# Bluetooth.net
KiCad netlist of a schematic drawn in EAGLE
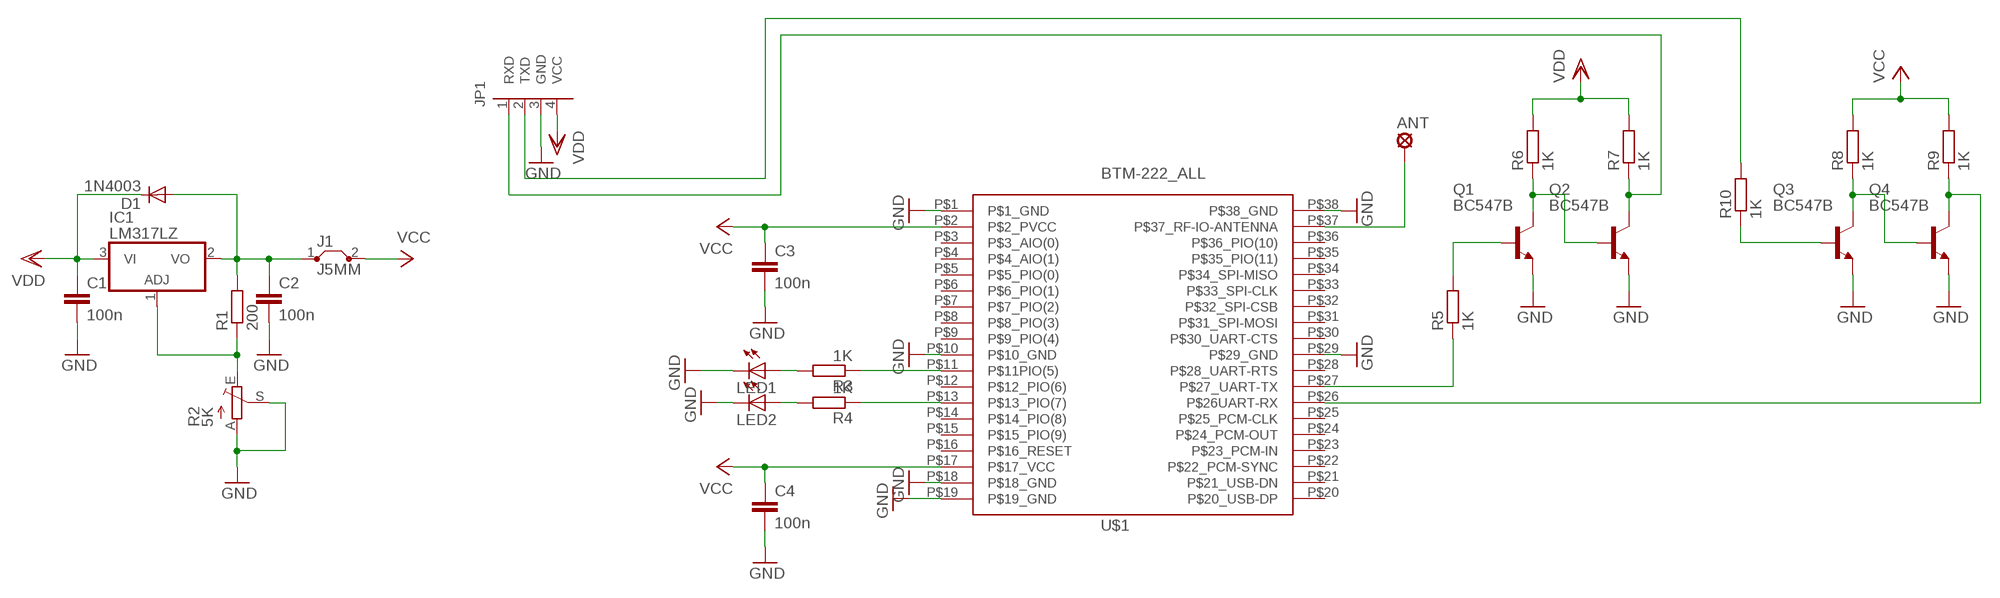
[diagram p0: schematic, sheet 1]

(export (version "E")
  (design (tool "Eeschema 10.0.6"))
  (components
    (comp (ref "ANT")
      (value "SE14")
      (footprint "eagle-import:SE14")
      (libsource (lib "eagle-import") (part "SE14"))
    )
    (comp (ref "C1")
      (value "100n")
      (footprint "eagle-import:C050-030X075")
      (libsource (lib "eagle-import") (part "C-EU050-030X075"))
    )
    (comp (ref "C2")
      (value "100n")
      (footprint "eagle-import:C050-030X075")
      (libsource (lib "eagle-import") (part "C-EU050-030X075"))
    )
    (comp (ref "C3")
      (value "100n")
      (footprint "eagle-import:C050-030X075")
      (libsource (lib "eagle-import") (part "C-EU050-030X075"))
    )
    (comp (ref "C4")
      (value "100n")
      (footprint "eagle-import:C050-030X075")
      (libsource (lib "eagle-import") (part "C-EU050-030X075"))
    )
    (comp (ref "D1")
      (value "1N4003")
      (footprint "eagle-import:DO41-10")
      (libsource (lib "eagle-import") (part "1N4004"))
    )
    (comp (ref "IC1")
      (value "LM317LZ")
      (footprint "eagle-import:TO92")
      (libsource (lib "eagle-import") (part "317LZLM"))
    )
    (comp (ref "J1")
      (value "J5MM")
      (footprint "eagle-import:05")
      (libsource (lib "eagle-import") (part "J5MM"))
    )
    (comp (ref "JP1")
      (value "RS232_TTL")
      (footprint "eagle-import:1X04")
      (libsource (lib "eagle-import") (part "RS232_TTL"))
    )
    (comp (ref "LED1")
      (value "LED3MM")
      (footprint "eagle-import:LED3MM")
      (libsource (lib "eagle-import") (part "LED3MM"))
    )
    (comp (ref "LED2")
      (value "LED3MM")
      (footprint "eagle-import:LED3MM")
      (libsource (lib "eagle-import") (part "LED3MM"))
    )
    (comp (ref "Q1")
      (value "BC547B")
      (footprint "eagle-import:TO92")
      (libsource (lib "eagle-import") (part "BC547B"))
    )
    (comp (ref "Q2")
      (value "BC547B")
      (footprint "eagle-import:TO92")
      (libsource (lib "eagle-import") (part "BC547B"))
    )
    (comp (ref "Q3")
      (value "BC547B")
      (footprint "eagle-import:TO92")
      (libsource (lib "eagle-import") (part "BC547B"))
    )
    (comp (ref "Q4")
      (value "BC547B")
      (footprint "eagle-import:TO92")
      (libsource (lib "eagle-import") (part "BC547B"))
    )
    (comp (ref "R1")
      (value "200")
      (footprint "eagle-import:0207_10")
      (libsource (lib "eagle-import") (part "R-EU_0207/10"))
    )
    (comp (ref "R2")
      (value "5K")
      (footprint "eagle-import:PT-10S")
      (libsource (lib "eagle-import") (part "TRIM_EU-PT10S"))
    )
    (comp (ref "R3")
      (value "1K")
      (footprint "eagle-import:0207_10")
      (libsource (lib "eagle-import") (part "R-EU_0207/10"))
    )
    (comp (ref "R4")
      (value "1K")
      (footprint "eagle-import:0207_10")
      (libsource (lib "eagle-import") (part "R-EU_0207/10"))
    )
    (comp (ref "R5")
      (value "1K")
      (footprint "eagle-import:0207_10")
      (libsource (lib "eagle-import") (part "R-EU_0207/10"))
    )
    (comp (ref "R6")
      (value "1K")
      (footprint "eagle-import:0207_10")
      (libsource (lib "eagle-import") (part "R-EU_0207/10"))
    )
    (comp (ref "R7")
      (value "1K")
      (footprint "eagle-import:0207_10")
      (libsource (lib "eagle-import") (part "R-EU_0207/10"))
    )
    (comp (ref "R8")
      (value "1K")
      (footprint "eagle-import:0207_10")
      (libsource (lib "eagle-import") (part "R-EU_0207/10"))
    )
    (comp (ref "R9")
      (value "1K")
      (footprint "eagle-import:0207_10")
      (libsource (lib "eagle-import") (part "R-EU_0207/10"))
    )
    (comp (ref "R10")
      (value "1K")
      (footprint "eagle-import:0207_10")
      (libsource (lib "eagle-import") (part "R-EU_0207/10"))
    )
    (comp (ref "U$1")
      (value "BTM-222_ALL")
      (footprint "eagle-import:BTM-222")
      (libsource (lib "eagle-import") (part "BTM-222_ALL"))
    )
  )
  (nets
    (net (code "1") (name "GND") (class "Default")
      (node (ref "C1") (pin "2") (pinfunction "2_2") (pintype "passive"))
      (node (ref "C2") (pin "2") (pinfunction "2_2") (pintype "passive"))
      (node (ref "C3") (pin "2") (pinfunction "2_2") (pintype "passive"))
      (node (ref "C4") (pin "2") (pinfunction "2_2") (pintype "passive"))
      (node (ref "JP1") (pin "3") (pinfunction "GND_3") (pintype "bidirectional"))
      (node (ref "LED1") (pin "K") (pinfunction "C_K") (pintype "passive"))
      (node (ref "LED2") (pin "K") (pinfunction "C_K") (pintype "passive"))
      (node (ref "Q1") (pin "1") (pinfunction "E_1") (pintype "passive"))
      (node (ref "Q2") (pin "1") (pinfunction "E_1") (pintype "passive"))
      (node (ref "Q3") (pin "1") (pinfunction "E_1") (pintype "passive"))
      (node (ref "Q4") (pin "1") (pinfunction "E_1") (pintype "passive"))
      (node (ref "R2") (pin "A") (pinfunction "A_A") (pintype "passive"))
      (node (ref "R2") (pin "S") (pinfunction "S_S") (pintype "passive"))
      (node (ref "U$1") (pin "P$1") (pinfunction "P$1_GND_P$1") (pintype "power_in"))
      (node (ref "U$1") (pin "P$10") (pinfunction "P$10_GND_P$10") (pintype "power_in"))
      (node (ref "U$1") (pin "P$18") (pinfunction "P$18_GND_P$18") (pintype "power_in"))
      (node (ref "U$1") (pin "P$19") (pinfunction "P$19_GND_P$19") (pintype "power_in"))
      (node (ref "U$1") (pin "P$29") (pinfunction "P$29_GND_P$29") (pintype "power_in"))
      (node (ref "U$1") (pin "P$38") (pinfunction "P$38_GND_P$38") (pintype "power_in"))
    )
    (net (code "2") (name "Net-(IC1-ADJ)") (class "Default")
      (node (ref "IC1") (pin "1") (pinfunction "ADJ_1") (pintype "input"))
      (node (ref "R1") (pin "1") (pinfunction "1_1") (pintype "passive"))
      (node (ref "R2") (pin "E") (pinfunction "E_E") (pintype "passive"))
    )
    (net (code "3") (name "Net-(IC1-VO)") (class "Default")
      (node (ref "C2") (pin "1") (pinfunction "1_1") (pintype "passive"))
      (node (ref "D1") (pin "A") (pinfunction "A_A") (pintype "passive"))
      (node (ref "IC1") (pin "2") (pinfunction "VO_2") (pintype "passive"))
      (node (ref "J1") (pin "1") (pinfunction "1_1") (pintype "passive"))
      (node (ref "R1") (pin "2") (pinfunction "2_2") (pintype "passive"))
    )
    (net (code "4") (name "Net-(JP1-RXD)") (class "Default")
      (node (ref "JP1") (pin "1") (pinfunction "RXD_1") (pintype "bidirectional"))
      (node (ref "Q2") (pin "3") (pinfunction "C_3") (pintype "passive"))
      (node (ref "R7") (pin "1") (pinfunction "1_1") (pintype "passive"))
    )
    (net (code "5") (name "Net-(JP1-TXD)") (class "Default")
      (node (ref "JP1") (pin "2") (pinfunction "TXD_2") (pintype "bidirectional"))
      (node (ref "R10") (pin "2") (pinfunction "2_2") (pintype "passive"))
    )
    (net (code "6") (name "Net-(LED1-PadA)") (class "Default")
      (node (ref "LED1") (pin "A") (pinfunction "A_A") (pintype "passive"))
      (node (ref "R3") (pin "2") (pinfunction "2_2") (pintype "passive"))
    )
    (net (code "7") (name "Net-(LED2-PadA)") (class "Default")
      (node (ref "LED2") (pin "A") (pinfunction "A_A") (pintype "passive"))
      (node (ref "R4") (pin "2") (pinfunction "2_2") (pintype "passive"))
    )
    (net (code "8") (name "Net-(Q1-B)") (class "Default")
      (node (ref "Q1") (pin "2") (pinfunction "B_2") (pintype "passive"))
      (node (ref "R5") (pin "2") (pinfunction "2_2") (pintype "passive"))
    )
    (net (code "9") (name "Net-(Q1-C)") (class "Default")
      (node (ref "Q1") (pin "3") (pinfunction "C_3") (pintype "passive"))
      (node (ref "Q2") (pin "2") (pinfunction "B_2") (pintype "passive"))
      (node (ref "R6") (pin "1") (pinfunction "1_1") (pintype "passive"))
    )
    (net (code "10") (name "Net-(Q3-B)") (class "Default")
      (node (ref "Q3") (pin "2") (pinfunction "B_2") (pintype "passive"))
      (node (ref "R10") (pin "1") (pinfunction "1_1") (pintype "passive"))
    )
    (net (code "11") (name "Net-(Q3-C)") (class "Default")
      (node (ref "Q3") (pin "3") (pinfunction "C_3") (pintype "passive"))
      (node (ref "Q4") (pin "2") (pinfunction "B_2") (pintype "passive"))
      (node (ref "R8") (pin "1") (pinfunction "1_1") (pintype "passive"))
    )
    (net (code "12") (name "Net-(Q4-C)") (class "Default")
      (node (ref "Q4") (pin "3") (pinfunction "C_3") (pintype "passive"))
      (node (ref "R9") (pin "1") (pinfunction "1_1") (pintype "passive"))
      (node (ref "U$1") (pin "P$26") (pinfunction "P$26UART-RX_P$26") (pintype "input"))
    )
    (net (code "13") (name "Net-(U$1-P$11PIO(5))") (class "Default")
      (node (ref "R3") (pin "1") (pinfunction "1_1") (pintype "passive"))
      (node (ref "U$1") (pin "P$11") (pinfunction "P$11PIO(5)_P$11") (pintype "bidirectional"))
    )
    (net (code "14") (name "Net-(U$1-P$13_PIO(7))") (class "Default")
      (node (ref "R4") (pin "1") (pinfunction "1_1") (pintype "passive"))
      (node (ref "U$1") (pin "P$13") (pinfunction "P$13_PIO(7)_P$13") (pintype "bidirectional"))
    )
    (net (code "15") (name "Net-(U$1-P$27_UART-TX)") (class "Default")
      (node (ref "R5") (pin "1") (pinfunction "1_1") (pintype "passive"))
      (node (ref "U$1") (pin "P$27") (pinfunction "P$27_UART-TX_P$27") (pintype "output"))
    )
    (net (code "16") (name "Net-(U$1-P$37_RF-IO-ANTENNA)") (class "Default")
      (node (ref "ANT") (pin "MP") (pinfunction "MP_MP") (pintype "passive"))
      (node (ref "U$1") (pin "P$37") (pinfunction "P$37_RF-IO-ANTENNA_P$37") (pintype "bidirectional"))
    )
    (net (code "17") (name "VCC") (class "Default")
      (node (ref "C3") (pin "1") (pinfunction "1_1") (pintype "passive"))
      (node (ref "C4") (pin "1") (pinfunction "1_1") (pintype "passive"))
      (node (ref "J1") (pin "2") (pinfunction "2_2") (pintype "passive"))
      (node (ref "R8") (pin "2") (pinfunction "2_2") (pintype "passive"))
      (node (ref "R9") (pin "2") (pinfunction "2_2") (pintype "passive"))
      (node (ref "U$1") (pin "P$17") (pinfunction "P$17_VCC_P$17") (pintype "power_in"))
      (node (ref "U$1") (pin "P$2") (pinfunction "P$2_PVCC_P$2") (pintype "power_in"))
    )
    (net (code "18") (name "VDD") (class "Default")
      (node (ref "C1") (pin "1") (pinfunction "1_1") (pintype "passive"))
      (node (ref "D1") (pin "C") (pinfunction "C_C") (pintype "passive"))
      (node (ref "IC1") (pin "3") (pinfunction "VI_3") (pintype "input"))
      (node (ref "JP1") (pin "4") (pinfunction "VCC_4") (pintype "bidirectional"))
      (node (ref "R6") (pin "2") (pinfunction "2_2") (pintype "passive"))
      (node (ref "R7") (pin "2") (pinfunction "2_2") (pintype "passive"))
    )
    (net (code "19") (name "unconnected-(U$1-P$3_AIO(0)-PadP$3)") (class "Default")
      (node (ref "U$1") (pin "P$3") (pinfunction "P$3_AIO(0)_P$3") (pintype "bidirectional"))
    )
    (net (code "20") (name "unconnected-(U$1-P$4_AIO(1)-PadP$4)") (class "Default")
      (node (ref "U$1") (pin "P$4") (pinfunction "P$4_AIO(1)_P$4") (pintype "bidirectional"))
    )
    (net (code "21") (name "unconnected-(U$1-P$5_PIO(0)-PadP$5)") (class "Default")
      (node (ref "U$1") (pin "P$5") (pinfunction "P$5_PIO(0)_P$5") (pintype "bidirectional"))
    )
    (net (code "22") (name "unconnected-(U$1-P$6_PIO(1)-PadP$6)") (class "Default")
      (node (ref "U$1") (pin "P$6") (pinfunction "P$6_PIO(1)_P$6") (pintype "bidirectional"))
    )
    (net (code "23") (name "unconnected-(U$1-P$7_PIO(2)-PadP$7)") (class "Default")
      (node (ref "U$1") (pin "P$7") (pinfunction "P$7_PIO(2)_P$7") (pintype "bidirectional"))
    )
    (net (code "24") (name "unconnected-(U$1-P$8_PIO(3)-PadP$8)") (class "Default")
      (node (ref "U$1") (pin "P$8") (pinfunction "P$8_PIO(3)_P$8") (pintype "bidirectional"))
    )
    (net (code "25") (name "unconnected-(U$1-P$9_PIO(4)-PadP$9)") (class "Default")
      (node (ref "U$1") (pin "P$9") (pinfunction "P$9_PIO(4)_P$9") (pintype "bidirectional"))
    )
    (net (code "26") (name "unconnected-(U$1-P$12_PIO(6)-PadP$12)") (class "Default")
      (node (ref "U$1") (pin "P$12") (pinfunction "P$12_PIO(6)_P$12") (pintype "bidirectional"))
    )
    (net (code "27") (name "unconnected-(U$1-P$14_PIO(8)-PadP$14)") (class "Default")
      (node (ref "U$1") (pin "P$14") (pinfunction "P$14_PIO(8)_P$14") (pintype "bidirectional"))
    )
    (net (code "28") (name "unconnected-(U$1-P$15_PIO(9)-PadP$15)") (class "Default")
      (node (ref "U$1") (pin "P$15") (pinfunction "P$15_PIO(9)_P$15") (pintype "bidirectional"))
    )
    (net (code "29") (name "unconnected-(U$1-P$16_RESET-PadP$16)") (class "Default")
      (node (ref "U$1") (pin "P$16") (pinfunction "P$16_RESET_P$16") (pintype "input"))
    )
    (net (code "30") (name "unconnected-(U$1-P$20_USB-DP-PadP$20)") (class "Default")
      (node (ref "U$1") (pin "P$20") (pinfunction "P$20_USB-DP_P$20") (pintype "bidirectional"))
    )
    (net (code "31") (name "unconnected-(U$1-P$21_USB-DN-PadP$21)") (class "Default")
      (node (ref "U$1") (pin "P$21") (pinfunction "P$21_USB-DN_P$21") (pintype "bidirectional"))
    )
    (net (code "32") (name "unconnected-(U$1-P$22_PCM-SYNC-PadP$22)") (class "Default")
      (node (ref "U$1") (pin "P$22") (pinfunction "P$22_PCM-SYNC_P$22") (pintype "bidirectional"))
    )
    (net (code "33") (name "unconnected-(U$1-P$23_PCM-IN-PadP$23)") (class "Default")
      (node (ref "U$1") (pin "P$23") (pinfunction "P$23_PCM-IN_P$23") (pintype "input"))
    )
    (net (code "34") (name "unconnected-(U$1-P$24_PCM-OUT-PadP$24)") (class "Default")
      (node (ref "U$1") (pin "P$24") (pinfunction "P$24_PCM-OUT_P$24") (pintype "output"))
    )
    (net (code "35") (name "unconnected-(U$1-P$25_PCM-CLK-PadP$25)") (class "Default")
      (node (ref "U$1") (pin "P$25") (pinfunction "P$25_PCM-CLK_P$25") (pintype "bidirectional"))
    )
    (net (code "36") (name "unconnected-(U$1-P$28_UART-RTS-PadP$28)") (class "Default")
      (node (ref "U$1") (pin "P$28") (pinfunction "P$28_UART-RTS_P$28") (pintype "output"))
    )
    (net (code "37") (name "unconnected-(U$1-P$30_UART-CTS-PadP$30)") (class "Default")
      (node (ref "U$1") (pin "P$30") (pinfunction "P$30_UART-CTS_P$30") (pintype "input"))
    )
    (net (code "38") (name "unconnected-(U$1-P$31_SPI-MOSI-PadP$31)") (class "Default")
      (node (ref "U$1") (pin "P$31") (pinfunction "P$31_SPI-MOSI_P$31") (pintype "input"))
    )
    (net (code "39") (name "unconnected-(U$1-P$32_SPI-CSB-PadP$32)") (class "Default")
      (node (ref "U$1") (pin "P$32") (pinfunction "P$32_SPI-CSB_P$32") (pintype "input"))
    )
    (net (code "40") (name "unconnected-(U$1-P$33_SPI-CLK-PadP$33)") (class "Default")
      (node (ref "U$1") (pin "P$33") (pinfunction "P$33_SPI-CLK_P$33") (pintype "input"))
    )
    (net (code "41") (name "unconnected-(U$1-P$34_SPI-MISO-PadP$34)") (class "Default")
      (node (ref "U$1") (pin "P$34") (pinfunction "P$34_SPI-MISO_P$34") (pintype "output"))
    )
    (net (code "42") (name "unconnected-(U$1-P$35_PIO(11)-PadP$35)") (class "Default")
      (node (ref "U$1") (pin "P$35") (pinfunction "P$35_PIO(11)_P$35") (pintype "bidirectional"))
    )
    (net (code "43") (name "unconnected-(U$1-P$36_PIO(10)-PadP$36)") (class "Default")
      (node (ref "U$1") (pin "P$36") (pinfunction "P$36_PIO(10)_P$36") (pintype "bidirectional"))
    )
  )
)
